# tumkibot1_audio_amplifier.net
KiCad netlist of a schematic drawn in EasyEDA Pro
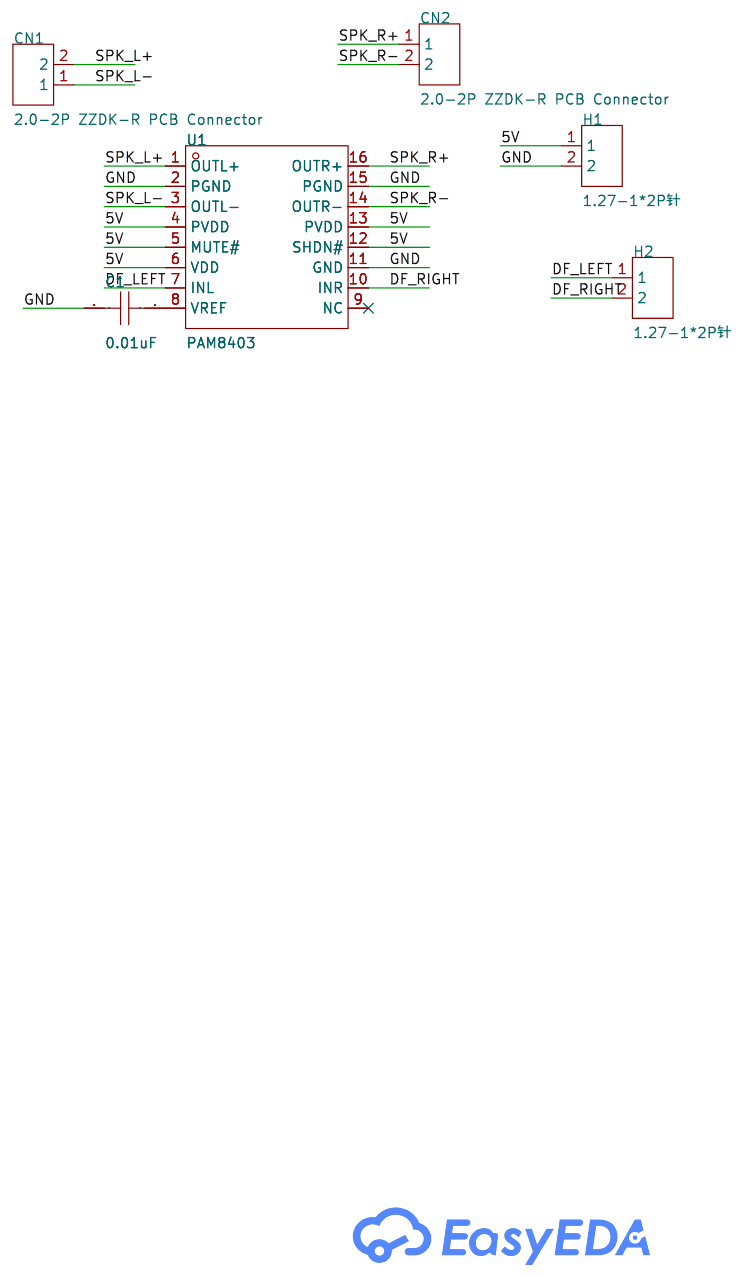
[diagram p0: schematic sheet]

(export (version "E")
  (design (tool "Eeschema 10.0.6"))
  (components
    (comp (ref "C1")
      (value "100nF")
      (footprint "easyedapro:C0603")
      (libsource (lib "easyedapro") (part "CAP"))
    )
    (comp (ref "CN1")
      (value "2.0-2P ZZDK-R PCB Connector")
      (footprint "easyedapro:CONN-TH_2.0-2P-ZZDK-R-PCB-CONNECTOR")
      (fields (field (name "Manufacturer") "SHOU HAN(首韩)"))
      (libsource (lib "easyedapro") (part "2.0-2P ZZDK-R PCB CONNECTOR"))
    )
    (comp (ref "CN2")
      (value "2.0-2P ZZDK-R PCB Connector")
      (footprint "easyedapro:CONN-TH_2.0-2P-ZZDK-R-PCB-CONNECTOR")
      (fields (field (name "Manufacturer") "SHOU HAN(首韩)"))
      (libsource (lib "easyedapro") (part "2.0-2P ZZDK-R PCB CONNECTOR"))
    )
    (comp (ref "H1")
      (value "1.27-1*2P针")
      (footprint "easyedapro:HDR-TH_2P-P1.27-V-M")
      (fields (field (name "Manufacturer") "BOOMELE(博穆精密)"))
      (libsource (lib "easyedapro") (part "1.27MM/1*2P"))
    )
    (comp (ref "H2")
      (value "1.27-1*2P针")
      (footprint "easyedapro:HDR-TH_2P-P1.27-V-M")
      (fields (field (name "Manufacturer") "BOOMELE(博穆精密)"))
      (libsource (lib "easyedapro") (part "1.27MM/1*2P"))
    )
    (comp (ref "U1")
      (value "PAM8403")
      (footprint "easyedapro:SOP-16_L10.0-W3.9-P1.27-LS6.0-BL")
      (description "Class:Class D Speaker Channels:- Voltage - Supply:2.2V~5.5V Voltage - Supply:2.2V~5.5V")
      (fields (field (name "Manufacturer") "Slkor(萨科微)"))
      (libsource (lib "easyedapro") (part "PAM8403"))
    )
  )
  (nets
    (net (code "1") (name "/5V") (class "Default")
      (node (ref "H1") (pin "1") (pinfunction "1_1") (pintype "unspecified"))
      (node (ref "U1") (pin "12") (pinfunction "SHDN#_12") (pintype "unspecified"))
      (node (ref "U1") (pin "13") (pinfunction "PVDD_13") (pintype "unspecified"))
      (node (ref "U1") (pin "4") (pinfunction "PVDD_4") (pintype "unspecified"))
      (node (ref "U1") (pin "5") (pinfunction "MUTE#_5") (pintype "unspecified"))
      (node (ref "U1") (pin "6") (pinfunction "VDD_6") (pintype "unspecified"))
    )
    (net (code "2") (name "/DF_LEFT") (class "Default")
      (node (ref "H2") (pin "1") (pinfunction "1_1") (pintype "unspecified"))
      (node (ref "U1") (pin "7") (pinfunction "INL_7") (pintype "unspecified"))
    )
    (net (code "3") (name "/DF_RIGHT") (class "Default")
      (node (ref "H2") (pin "2") (pinfunction "2_2") (pintype "unspecified"))
      (node (ref "U1") (pin "10") (pinfunction "INR_10") (pintype "unspecified"))
    )
    (net (code "4") (name "/GND") (class "Default")
      (node (ref "C1") (pin "2") (pinfunction "2_2") (pintype "input"))
      (node (ref "H1") (pin "2") (pinfunction "2_2") (pintype "unspecified"))
      (node (ref "U1") (pin "11") (pinfunction "GND_11") (pintype "unspecified"))
      (node (ref "U1") (pin "15") (pinfunction "PGND_15") (pintype "unspecified"))
      (node (ref "U1") (pin "2") (pinfunction "PGND_2") (pintype "unspecified"))
    )
    (net (code "5") (name "/SPK_L+") (class "Default")
      (node (ref "CN1") (pin "2") (pinfunction "2_2") (pintype "unspecified"))
      (node (ref "U1") (pin "1") (pinfunction "OUTL+_1") (pintype "unspecified"))
    )
    (net (code "6") (name "/SPK_L-") (class "Default")
      (node (ref "CN1") (pin "1") (pinfunction "1_1") (pintype "unspecified"))
      (node (ref "U1") (pin "3") (pinfunction "OUTL-_3") (pintype "unspecified"))
    )
    (net (code "7") (name "/SPK_R+") (class "Default")
      (node (ref "CN2") (pin "1") (pinfunction "1_1") (pintype "unspecified"))
      (node (ref "U1") (pin "16") (pinfunction "OUTR+_16") (pintype "unspecified"))
    )
    (net (code "8") (name "/SPK_R-") (class "Default")
      (node (ref "CN2") (pin "2") (pinfunction "2_2") (pintype "unspecified"))
      (node (ref "U1") (pin "14") (pinfunction "OUTR-_14") (pintype "unspecified"))
    )
    (net (code "9") (name "Net-(U1-VREF)") (class "Default")
      (node (ref "C1") (pin "1") (pinfunction "1_1") (pintype "input"))
      (node (ref "U1") (pin "8") (pinfunction "VREF_8") (pintype "unspecified"))
    )
    (net (code "10") (name "unconnected-(U1-NC-Pad9)") (class "Default")
      (node (ref "U1") (pin "9") (pinfunction "NC_9") (pintype "unspecified+no_connect"))
    )
  )
)
